# 12-Flow_meter.net
KiCad netlist of a schematic drawn in Altium Designer
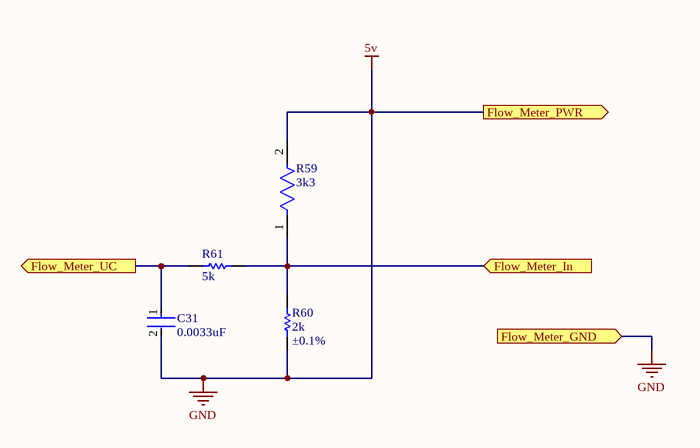
[diagram p0: 12-Flow meter.SchDoc]

(export (version "E")
  (design (tool "Eeschema 10.0.6"))
  (components
    (comp (ref "C31")
      (value "0.0033uF")
      (footprint "FP-GRM188-0_1-e0_2_0_5-IPC_A")
      (description "Chip Multilayer Ceramic Capacitors for General Purpose, 0603, 3300pF, C0G, 30ppm/°C, 5%, 50V")
      (fields (field (name "TOLERANCE") "5%") (field (name "VOLTAGE") "50V"))
      (libsource (lib "Altium Content Vault") (part "11868f565c42a9108669ba33697ecf6"))
    )
    (comp (ref "R59")
      (value "3k3")
      (footprint "FP-RC0603-0_55-MFG")
      (fields (field (name "TOLERANCE") "1%"))
      (libsource (lib "Altium Content Vault") (part "1029c3af85768c4190bb7ad29bc67b5"))
    )
    (comp (ref "R60")
      (value "2k")
      (footprint "1608[0603]")
      (description "Resistor")
      (fields
        (field (name "MANUFACTURER") "Yageo")
        (field (name "MANUFACTURER PART NUMBER") "AT0603BRD072KL")
        (field (name "TOLERANCE") "±0.1%")
      )
      (libsource (lib "Miscellaneous Devices") (part "Res1"))
    )
    (comp (ref "R61")
      (value "5k")
      (footprint "1608[0603]")
      (description "Resistor")
      (fields
        (field (name "MANUFACTURER") "Yageo")
        (field (name "MANUFACTURER PART NUMBER") "AT0603BRD072KL")
      )
      (libsource (lib "Miscellaneous Devices") (part "Res1"))
    )
  )
  (nets
    (net (code "1") (name "/Flow_Meter_In") (class "Default")
      (node (ref "R59") (pin "1") (pinfunction "1_1") (pintype "passive"))
      (node (ref "R60") (pin "2") (pinfunction "2_2") (pintype "passive"))
      (node (ref "R61") (pin "1") (pinfunction "1_1") (pintype "passive"))
    )
    (net (code "2") (name "/Flow_Meter_UC") (class "Default")
      (node (ref "C31") (pin "1") (pinfunction "1_1") (pintype "passive"))
      (node (ref "R61") (pin "2") (pinfunction "2_2") (pintype "passive"))
    )
    (net (code "3") (name "5v") (class "Default")
      (node (ref "C31") (pin "2") (pinfunction "2_2") (pintype "passive"))
      (node (ref "R59") (pin "2") (pinfunction "2_2") (pintype "passive"))
      (node (ref "R60") (pin "1") (pinfunction "1_1") (pintype "passive"))
    )
  )
)
